# 02_-_BLOCK_DIAGRAM.net
KiCad netlist of a schematic drawn in Altium Designer
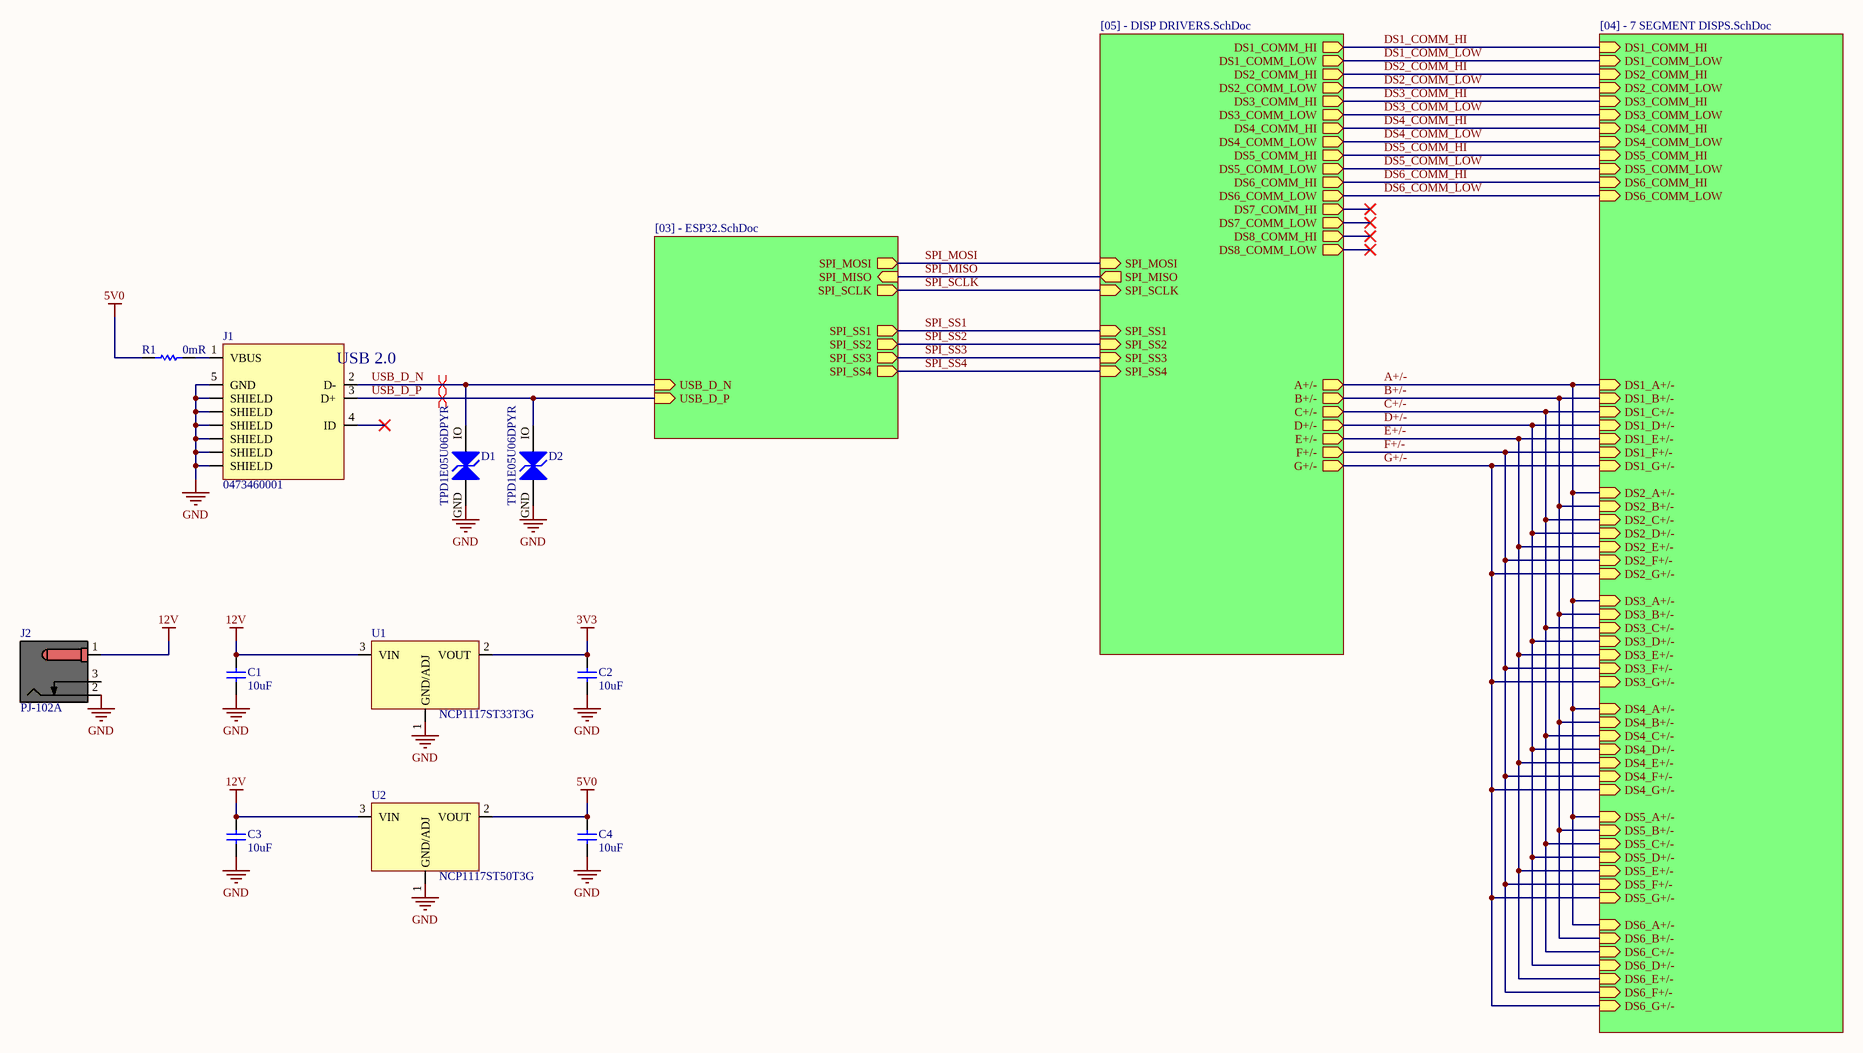
[diagram p0: [02] - BLOCK DIAGRAM.SchDoc]

(export (version "E")
  (design (tool "Eeschema 10.0.6"))
  (components
    (comp (ref "C1")
      (value "10uF")
      (footprint "INCH 0805 - METRIC 2012 - H140")
      (description "CAP CER 10UF 25V X5R 0805")
      (fields
        (field (name "MANUFACTURER") "Murata")
        (field (name "MANUFACTURER PART NUMBER") "GRM21BR61E106MA73L")
      )
      (libsource (lib "Capacitors") (part "GRM21BR61E106MA73L"))
    )
    (comp (ref "C2")
      (value "10uF")
      (footprint "INCH 0805 - METRIC 2012 - H140")
      (description "CAP CER 10UF 25V X5R 0805")
      (fields
        (field (name "MANUFACTURER") "Murata")
        (field (name "MANUFACTURER PART NUMBER") "GRM21BR61E106MA73L")
      )
      (libsource (lib "Capacitors") (part "GRM21BR61E106MA73L"))
    )
    (comp (ref "C3")
      (value "10uF")
      (footprint "INCH 0805 - METRIC 2012 - H140")
      (description "CAP CER 10UF 25V X5R 0805")
      (fields
        (field (name "MANUFACTURER") "Murata")
        (field (name "MANUFACTURER PART NUMBER") "GRM21BR61E106MA73L")
      )
      (libsource (lib "Capacitors") (part "GRM21BR61E106MA73L"))
    )
    (comp (ref "C4")
      (value "10uF")
      (footprint "INCH 0805 - METRIC 2012 - H140")
      (description "CAP CER 10UF 25V X5R 0805")
      (fields
        (field (name "MANUFACTURER") "Murata")
        (field (name "MANUFACTURER PART NUMBER") "GRM21BR61E106MA73L")
      )
      (libsource (lib "Capacitors") (part "GRM21BR61E106MA73L"))
    )
    (comp (ref "D1")
      (value "TPD1E05U06DPYR")
      (footprint "DIODFN100X60X50-2")
      (description "TVS DIODE 5.5VWM 14VC 2X2SON")
      (fields (field (name "MANUFACTURER") "Texas Instruments"))
      (libsource (lib "ESD Devices") (part "TPD1E05U06DPYR"))
    )
    (comp (ref "D2")
      (value "TPD1E05U06DPYR")
      (footprint "DIODFN100X60X50-2")
      (description "TVS DIODE 5.5VWM 14VC 2X2SON")
      (fields (field (name "MANUFACTURER") "Texas Instruments"))
      (libsource (lib "ESD Devices") (part "TPD1E05U06DPYR"))
    )
    (comp (ref "J1")
      (value "0473460001")
      (footprint "MOLEX_047346-0001")
      (description "Conn Micro USB Type B RCP 5 POS 0.65mm Solder RA SMD 5 Terminal 1 Port Embossed T/R")
      (fields (field (name "MANUFACTURER") "Molex"))
      (libsource (lib "Connectors") (part "0473460001"))
    )
    (comp (ref "J2")
      (value "PJ-102A")
      (footprint "CUI_PJ-102A")
      (description "PJ-102 Series 2 x 6.5 mm 16 V Horizontal Power Jack w/ Tapered PC Pins")
      (fields (field (name "MANUFACTURER") "CUI"))
      (libsource (lib "Connectors") (part "PJ-102A"))
    )
    (comp (ref "R1")
      (value "0mR")
      (footprint "INCH 0603 - METRIC 1508 - H050")
      (description "RES SMD 0 OHM JUMPER 1/10W 0603")
      (fields
        (field (name "MANUFACTURER") "Panasonic")
        (field (name "MANUFACTURER PART NUMBER") "ERJ-3GEY0R00V")
      )
      (libsource (lib "Resistors") (part "ERJ-3GEY0R00V"))
    )
    (comp (ref "U1")
      (value "NCP1117ST33T3G")
      (footprint "SOT223-4P230_700X180L90X70")
      (description "IC REG LINEAR 3.3V 1A SOT223")
      (fields (field (name "MANUFACTURER") "ON Semiconductor"))
      (libsource (lib "Voltage Regulators - Linear") (part "NCP1117ST33T3G"))
    )
    (comp (ref "U2")
      (value "NCP1117ST50T3G")
      (footprint "SOT223-4P230_700X180L90X70")
      (description "IC REG LINEAR 5V 1A SOT223")
      (fields (field (name "MANUFACTURER") "ON Semiconductor") (field (name "TOLERANCE") "1%"))
      (libsource (lib "Voltage Regulators - Linear") (part "NCP1117ST50T3G"))
    )
  )
  (nets
    (net (code "31") (name "/USB_D_N") (class "Default")
      (node (ref "D1") (pin "IO") (pinfunction "IO_IO") (pintype "passive"))
      (node (ref "J1") (pin "2") (pinfunction "D-_2") (pintype "passive"))
    )
    (net (code "32") (name "/USB_D_P") (class "Default")
      (node (ref "D2") (pin "IO") (pinfunction "IO_IO") (pintype "passive"))
      (node (ref "J1") (pin "3") (pinfunction "D+_3") (pintype "passive"))
    )
    (net (code "33") (name "3V3") (class "Default")
      (node (ref "C2") (pin "1") (pintype "passive"))
      (node (ref "U1") (pin "2") (pinfunction "VOUT_2") (pintype "passive"))
    )
    (net (code "34") (name "5V0") (class "Default")
      (node (ref "C4") (pin "1") (pintype "passive"))
      (node (ref "R1") (pin "1") (pintype "passive"))
      (node (ref "U2") (pin "2") (pinfunction "VOUT_2") (pintype "passive"))
    )
    (net (code "35") (name "12V") (class "Default")
      (node (ref "C1") (pin "1") (pintype "passive"))
      (node (ref "C3") (pin "1") (pintype "passive"))
      (node (ref "J2") (pin "1") (pintype "passive"))
      (node (ref "U1") (pin "3") (pinfunction "VIN_3") (pintype "passive"))
      (node (ref "U2") (pin "3") (pinfunction "VIN_3") (pintype "passive"))
    )
    (net (code "36") (name "GND") (class "Default")
      (node (ref "C1") (pin "2") (pintype "passive"))
      (node (ref "C2") (pin "2") (pintype "passive"))
      (node (ref "C3") (pin "2") (pintype "passive"))
      (node (ref "C4") (pin "2") (pintype "passive"))
      (node (ref "D1") (pin "GND") (pinfunction "GND_GND") (pintype "passive"))
      (node (ref "D2") (pin "GND") (pinfunction "GND_GND") (pintype "passive"))
      (node (ref "J1") (pin "0") (pinfunction "SHIELD_0") (pintype "passive"))
      (node (ref "J1") (pin "5") (pinfunction "GND_5") (pintype "passive"))
      (node (ref "J2") (pin "2") (pintype "passive"))
      (node (ref "U1") (pin "1") (pinfunction "GND/ADJ_1") (pintype "passive"))
      (node (ref "U2") (pin "1") (pinfunction "GND/ADJ_1") (pintype "passive"))
    )
    (net (code "37") (name "Net-(J1-VBUS)") (class "Default")
      (node (ref "J1") (pin "1") (pinfunction "VBUS_1") (pintype "passive"))
      (node (ref "R1") (pin "2") (pintype "passive"))
    )
    (net (code "38") (name "unconnected-(J1-ID-Pad4)") (class "Default")
      (node (ref "J1") (pin "4") (pinfunction "ID_4") (pintype "passive+no_connect"))
    )
    (net (code "39") (name "unconnected-(J2-Pad3)") (class "Default")
      (node (ref "J2") (pin "3") (pintype "passive"))
    )
  )
)
